# AstroEQ_PTH_MK2.net
KiCad netlist of a schematic drawn in EAGLE
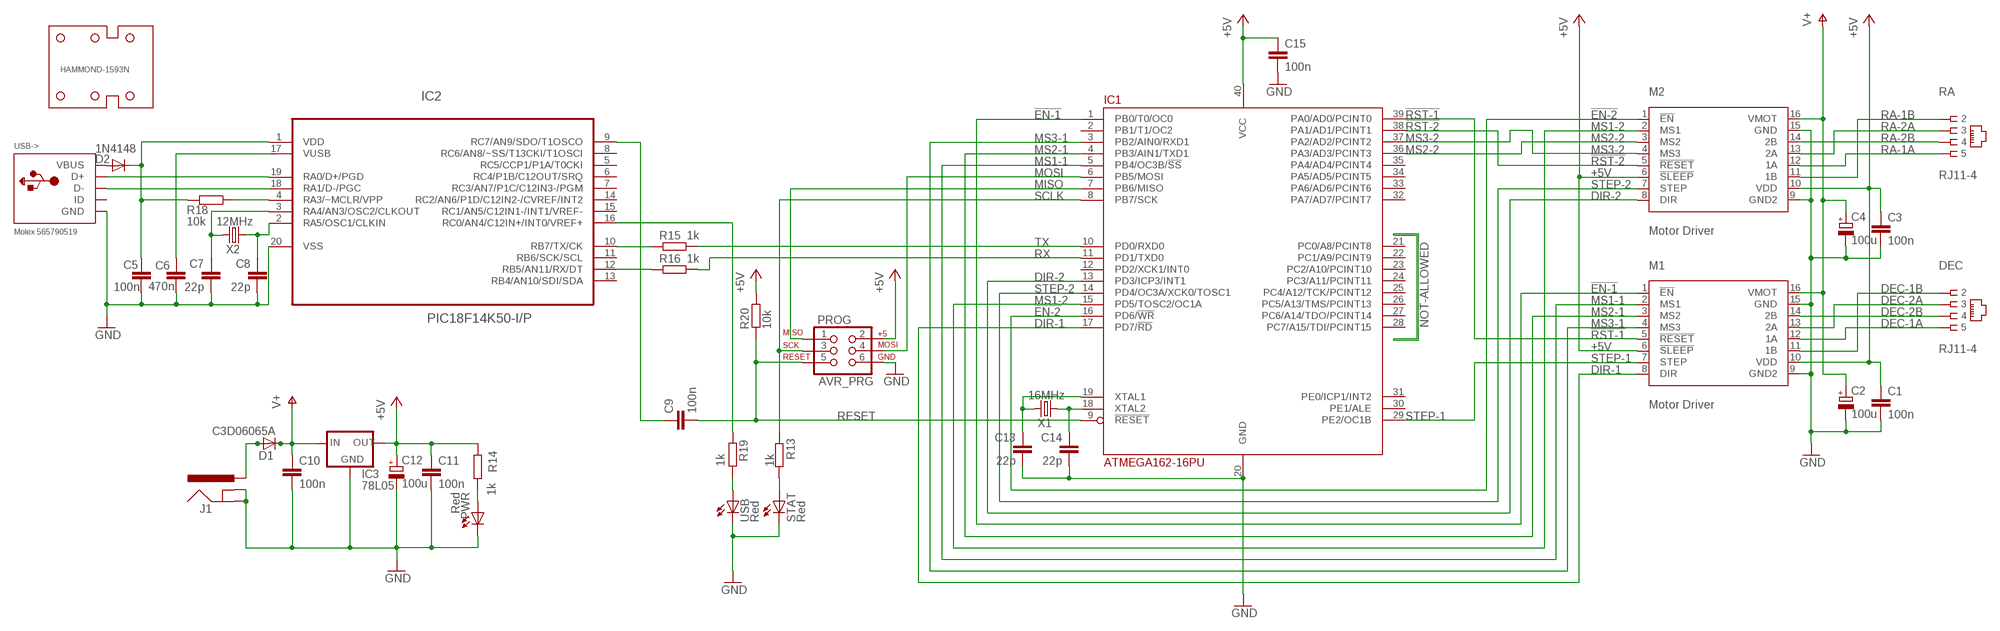
[diagram p0: schematic, sheet 1]

(export (version "E")
  (design (tool "Eeschema 10.0.6"))
  (components
    (comp (ref "C1")
      (value "100n")
      (footprint "eagle-import:C025-024X044")
      (fields (field (name "MF") "AVX") (field (name "MPN") "SR205C104KAR"))
      (libsource (lib "eagle-import") (part "resistor_C-EU025-024X044"))
    )
    (comp (ref "C2")
      (value "100u")
      (footprint "eagle-import:E2,5-7")
      (fields (field (name "MF") "MULTICOMP") (field (name "MPN") "MCGPR25V107M6.3X11"))
      (libsource (lib "eagle-import") (part "CPOL-EUE2.5-7"))
    )
    (comp (ref "C3")
      (value "100n")
      (footprint "eagle-import:C025-024X044")
      (fields (field (name "MF") "AVX") (field (name "MPN") "SR205C104KAR"))
      (libsource (lib "eagle-import") (part "resistor_C-EU025-024X044"))
    )
    (comp (ref "C4")
      (value "100u")
      (footprint "eagle-import:E2,5-7")
      (fields (field (name "MF") "MULTICOMP") (field (name "MPN") "MCGPR25V107M6.3X11"))
      (libsource (lib "eagle-import") (part "CPOL-EUE2.5-7"))
    )
    (comp (ref "C5")
      (value "100n")
      (footprint "eagle-import:C025-024X044")
      (fields (field (name "MF") "AVX") (field (name "MPN") "SR205C104KAR"))
      (libsource (lib "eagle-import") (part "resistor_C-EU025-024X044"))
    )
    (comp (ref "C6")
      (value "470n")
      (footprint "eagle-import:C025-024X044")
      (fields (field (name "MF") "KEMET") (field (name "MPN") "C320C474M5U5TA"))
      (libsource (lib "eagle-import") (part "C-EU025-024X044"))
    )
    (comp (ref "C7")
      (value "22p")
      (footprint "eagle-import:C025-024X044")
      (fields (field (name "MF") "AVX") (field (name "MPN") "SR151A220JAR"))
      (libsource (lib "eagle-import") (part "C-EU025-024X044"))
    )
    (comp (ref "C8")
      (value "22p")
      (footprint "eagle-import:C025-024X044")
      (fields (field (name "MF") "AVX") (field (name "MPN") "SR151A220JAR"))
      (libsource (lib "eagle-import") (part "C-EU025-024X044"))
    )
    (comp (ref "C9")
      (value "100n")
      (footprint "eagle-import:C025-024X044")
      (fields (field (name "MF") "AVX") (field (name "MPN") "SR205C104KAR"))
      (libsource (lib "eagle-import") (part "resistor_C-EU025-024X044"))
    )
    (comp (ref "C10")
      (value "100n")
      (footprint "eagle-import:C025-024X044")
      (fields (field (name "MF") "AVX") (field (name "MPN") "SR205C104KAR"))
      (libsource (lib "eagle-import") (part "resistor_C-EU025-024X044"))
    )
    (comp (ref "C11")
      (value "100n")
      (footprint "eagle-import:C025-024X044")
      (fields (field (name "MF") "AVX") (field (name "MPN") "SR205C104KAR"))
      (libsource (lib "eagle-import") (part "resistor_C-EU025-024X044"))
    )
    (comp (ref "C12")
      (value "100u")
      (footprint "eagle-import:E2,5-7")
      (fields (field (name "MF") "MULTICOMP") (field (name "MPN") "MCGPR25V107M6.3X11"))
      (libsource (lib "eagle-import") (part "CPOL-EUE2.5-7"))
    )
    (comp (ref "C13")
      (value "22p")
      (footprint "eagle-import:C025-024X044")
      (fields (field (name "MF") "AVX") (field (name "MPN") "SR151A220JAR"))
      (libsource (lib "eagle-import") (part "C-EU025-024X044"))
    )
    (comp (ref "C14")
      (value "22p")
      (footprint "eagle-import:C025-024X044")
      (fields (field (name "MF") "AVX") (field (name "MPN") "SR151A220JAR"))
      (libsource (lib "eagle-import") (part "C-EU025-024X044"))
    )
    (comp (ref "C15")
      (value "100n")
      (footprint "eagle-import:C025-024X044")
      (fields (field (name "MF") "AVX") (field (name "MPN") "SR205C104KAR"))
      (libsource (lib "eagle-import") (part "resistor_C-EU025-024X044"))
    )
    (comp (ref "D1")
      (value "C3D06065A")
      (footprint "eagle-import:C221B1A")
      (fields (field (name "MF") "CREE"))
      (libsource (lib "eagle-import") (part "MUR820"))
    )
    (comp (ref "D2")
      (value "1N4148")
      (footprint "eagle-import:DIODE-1N4148")
      (fields (field (name "MF") "MULTICOMP") (field (name "MPN") "1N4148."))
      (libsource (lib "eagle-import") (part "DIODE1N4148"))
    )
    (comp (ref "DEC")
      (value "RJ11-4")
      (footprint "eagle-import:RJ11-NO_SHIELD-4")
      (fields (field (name "MF") "MOLEX") (field (name "MPN") "95501-2641"))
      (libsource (lib "eagle-import") (part "RJ11-4"))
    )
    (comp (ref "HAMMOND-1593N")
      (value "HAMMOND-1593N")
      (footprint "eagle-import:HAMMOND-1593N")
      (fields (field (name "MF") "HAMMOND") (field (name "MPN") "1593NBK"))
      (libsource (lib "eagle-import") (part "HAMMOND-1593N"))
    )
    (comp (ref "IC1")
      (value "ATMEGA162-16PU")
      (footprint "eagle-import:DIL40")
      (fields (field (name "MF") "ATMEL"))
      (libsource (lib "eagle-import") (part "ATMEGA162-16PU"))
    )
    (comp (ref "IC2")
      (value "PIC18F14K50-I/P")
      (footprint "eagle-import:DIL20")
      (fields (field (name "MF") "MICROCHIP"))
      (libsource (lib "eagle-import") (part "PIC18F14K50-I/P"))
    )
    (comp (ref "IC3")
      (value "78L05")
      (footprint "eagle-import:TO-92")
      (fields (field (name "MF") "FAIRCHILD SEMICONDUCTOR") (field (name "MPN") "LM78L05ACZX"))
      (libsource (lib "eagle-import") (part "V_REG_78XXTO-92"))
    )
    (comp (ref "J1")
      (value "POWER_JACKPTH")
      (footprint "eagle-import:POWER_JACK_PTH")
      (fields (field (name "MF") "MULTICOMP") (field (name "MPN") "MJ-179PH"))
      (libsource (lib "eagle-import") (part "POWER_JACKPTH"))
    )
    (comp (ref "M1")
      (value "Motor Driver")
      (footprint "eagle-import:DIP16-W")
      (fields (field (name "MF") "SAMTEC") (field (name "MPN") "CES-116-01-T-S"))
      (libsource (lib "eagle-import") (part "A4983CARRIER"))
    )
    (comp (ref "M2")
      (value "Motor Driver")
      (footprint "eagle-import:DIP16-W")
      (fields (field (name "MF") "SAMTEC") (field (name "MPN") "CES-116-01-T-S"))
      (libsource (lib "eagle-import") (part "A4983CARRIER"))
    )
    (comp (ref "PROG")
      (value "AVR_PRG")
      (footprint "eagle-import:2X3")
      (fields (field (name "MF") "TE CONNECTIVITY / AMP") (field (name "MPN") "826632-3"))
      (libsource (lib "eagle-import") (part "AVR_SPI_PRG_6PTH"))
    )
    (comp (ref "PWR")
      (value "Red")
      (footprint "eagle-import:LED3MM")
      (fields (field (name "MF") "KINGBRIGHT") (field (name "MPN") "L-424HDT"))
      (libsource (lib "eagle-import") (part "LED3MM"))
    )
    (comp (ref "R13")
      (value "1k")
      (footprint "eagle-import:0204_7")
      (fields (field (name "MF") "MULTICOMP") (field (name "MPN") "MF12 1K"))
      (libsource (lib "eagle-import") (part "rcl_R-EU_0204/7"))
    )
    (comp (ref "R14")
      (value "1k")
      (footprint "eagle-import:0204_7")
      (fields (field (name "MF") "MULTICOMP") (field (name "MPN") "MF12 1K"))
      (libsource (lib "eagle-import") (part "rcl_R-EU_0204/7"))
    )
    (comp (ref "R15")
      (value "1k")
      (footprint "eagle-import:0204_7")
      (fields (field (name "MF") "MULTICOMP") (field (name "MPN") "MF12 1K"))
      (libsource (lib "eagle-import") (part "R-EU_0204/7"))
    )
    (comp (ref "R16")
      (value "1k")
      (footprint "eagle-import:0204_7")
      (fields (field (name "MF") "MULTICOMP") (field (name "MPN") "MF12 1K"))
      (libsource (lib "eagle-import") (part "R-EU_0204/7"))
    )
    (comp (ref "R18")
      (value "10k")
      (footprint "eagle-import:0204_7")
      (fields (field (name "MF") "MULTICOMP") (field (name "MPN") "MF12 10K"))
      (libsource (lib "eagle-import") (part "rcl_R-EU_0204/7"))
    )
    (comp (ref "R19")
      (value "1k")
      (footprint "eagle-import:0204_7")
      (fields (field (name "MF") "MULTICOMP") (field (name "MPN") "MF12 1K"))
      (libsource (lib "eagle-import") (part "rcl_R-EU_0204/7"))
    )
    (comp (ref "R20")
      (value "10k")
      (footprint "eagle-import:0204_7")
      (fields (field (name "MF") "MULTICOMP") (field (name "MPN") "MF12 10K"))
      (libsource (lib "eagle-import") (part "rcl_R-EU_0204/7"))
    )
    (comp (ref "RA")
      (value "RJ11-4")
      (footprint "eagle-import:RJ11-NO_SHIELD-4")
      (fields (field (name "MF") "MOLEX") (field (name "MPN") "95501-2641"))
      (libsource (lib "eagle-import") (part "RJ11-4"))
    )
    (comp (ref "STAT")
      (value "Red")
      (footprint "eagle-import:LED3MM")
      (fields (field (name "MF") "KINGBRIGHT") (field (name "MPN") "L-424HDT"))
      (libsource (lib "eagle-import") (part "LED3MM"))
    )
    (comp (ref "USB")
      (value "Red")
      (footprint "eagle-import:LED3MM")
      (fields (field (name "MF") "KINGBRIGHT") (field (name "MPN") "L-424HDT"))
      (libsource (lib "eagle-import") (part "LED3MM"))
    )
    (comp (ref "USB->")
      (value "Molex 565790519")
      (footprint "eagle-import:USB-MINIB-THM-MOLEX")
      (fields (field (name "MF") "MOLEX") (field (name "MPN") "565790519"))
      (libsource (lib "eagle-import") (part "USBMOLEX"))
    )
    (comp (ref "X1")
      (value "16MHz")
      (footprint "eagle-import:HC49US")
      (fields (field (name "MF") "TXC") (field (name "MPN") "9B-16.000MEEJ-B"))
      (libsource (lib "eagle-import") (part "CRYSTALHC49US"))
    )
    (comp (ref "X2")
      (value "12MHz")
      (footprint "eagle-import:HC49US")
      (fields (field (name "MF") "TXC") (field (name "MPN") "9B-12.000MAAJ-B"))
      (libsource (lib "eagle-import") (part "CRYSTALHC49US"))
    )
  )
  (nets
    (net (code "1") (name "+5V") (class "Default")
      (node (ref "C1") (pin "1") (pinfunction "1_1") (pintype "passive"))
      (node (ref "C11") (pin "1") (pinfunction "1_1") (pintype "passive"))
      (node (ref "C12") (pin "+") (pinfunction "+_+") (pintype "passive"))
      (node (ref "C15") (pin "1") (pinfunction "1_1") (pintype "passive"))
      (node (ref "C3") (pin "1") (pinfunction "1_1") (pintype "passive"))
      (node (ref "IC1") (pin "40") (pinfunction "VCC_40") (pintype "power_in"))
      (node (ref "IC3") (pin "1") (pinfunction "OUT_1") (pintype "power_in"))
      (node (ref "M1") (pin "10") (pinfunction "VDD_10") (pintype "power_in"))
      (node (ref "M1") (pin "6") (pinfunction "~{SLEEP}_6") (pintype "input"))
      (node (ref "M2") (pin "10") (pinfunction "VDD_10") (pintype "power_in"))
      (node (ref "M2") (pin "6") (pinfunction "~{SLEEP}_6") (pintype "input"))
      (node (ref "PROG") (pin "2") (pinfunction "2_2") (pintype "passive"))
      (node (ref "R14") (pin "1") (pinfunction "1_1") (pintype "passive"))
      (node (ref "R20") (pin "2") (pinfunction "2_2") (pintype "passive"))
    )
    (net (code "2") (name "/DEC-1A") (class "Default")
      (node (ref "DEC") (pin "5") (pinfunction "5_5") (pintype "passive"))
      (node (ref "M1") (pin "12") (pinfunction "1A_12") (pintype "output"))
    )
    (net (code "3") (name "/DEC-1B") (class "Default")
      (node (ref "DEC") (pin "2") (pinfunction "2_2") (pintype "passive"))
      (node (ref "M1") (pin "11") (pinfunction "1B_11") (pintype "output"))
    )
    (net (code "4") (name "/DEC-2A") (class "Default")
      (node (ref "DEC") (pin "3") (pinfunction "3_3") (pintype "passive"))
      (node (ref "M1") (pin "13") (pinfunction "2A_13") (pintype "output"))
    )
    (net (code "5") (name "/DEC-2B") (class "Default")
      (node (ref "DEC") (pin "4") (pinfunction "4_4") (pintype "passive"))
      (node (ref "M1") (pin "14") (pinfunction "2B_14") (pintype "output"))
    )
    (net (code "6") (name "/DIR-1") (class "Default")
      (node (ref "IC1") (pin "17") (pinfunction "PD7/~{RD}_17") (pintype "bidirectional"))
      (node (ref "M1") (pin "8") (pinfunction "DIR_8") (pintype "input"))
    )
    (net (code "7") (name "/DIR-2") (class "Default")
      (node (ref "IC1") (pin "13") (pinfunction "PD3/ICP3/INT1_13") (pintype "bidirectional"))
      (node (ref "M2") (pin "8") (pinfunction "DIR_8") (pintype "input"))
    )
    (net (code "8") (name "/MISO") (class "Default")
      (node (ref "IC1") (pin "7") (pinfunction "PB6/MISO_7") (pintype "bidirectional"))
      (node (ref "PROG") (pin "1") (pinfunction "1_1") (pintype "passive"))
    )
    (net (code "9") (name "/MOSI") (class "Default")
      (node (ref "IC1") (pin "6") (pinfunction "PB5/MOSI_6") (pintype "bidirectional"))
      (node (ref "PROG") (pin "4") (pinfunction "4_4") (pintype "passive"))
    )
    (net (code "10") (name "/MS1-1") (class "Default")
      (node (ref "IC1") (pin "5") (pinfunction "PB4/OC3B/~{SS}_5") (pintype "bidirectional"))
      (node (ref "M1") (pin "2") (pinfunction "MS1_2") (pintype "input"))
    )
    (net (code "11") (name "/MS1-2") (class "Default")
      (node (ref "IC1") (pin "15") (pinfunction "PD5/TOSC2/OC1A_15") (pintype "bidirectional"))
      (node (ref "M2") (pin "2") (pinfunction "MS1_2") (pintype "input"))
    )
    (net (code "12") (name "/MS2-1") (class "Default")
      (node (ref "IC1") (pin "4") (pinfunction "PB3/AIN1/TXD1_4") (pintype "bidirectional"))
      (node (ref "M1") (pin "3") (pinfunction "MS2_3") (pintype "input"))
    )
    (net (code "13") (name "/MS2-2") (class "Default")
      (node (ref "IC1") (pin "36") (pinfunction "PA3/AD3/PCINT3_36") (pintype "bidirectional"))
      (node (ref "M2") (pin "3") (pinfunction "MS2_3") (pintype "input"))
    )
    (net (code "14") (name "/MS3-1") (class "Default")
      (node (ref "IC1") (pin "3") (pinfunction "PB2/AIN0/RXD1_3") (pintype "bidirectional"))
      (node (ref "M1") (pin "4") (pinfunction "MS3_4") (pintype "input"))
    )
    (net (code "15") (name "/MS3-2") (class "Default")
      (node (ref "IC1") (pin "37") (pinfunction "PA2/AD2/PCINT2_37") (pintype "bidirectional"))
      (node (ref "M2") (pin "4") (pinfunction "MS3_4") (pintype "input"))
    )
    (net (code "16") (name "/RA-1A") (class "Default")
      (node (ref "M2") (pin "12") (pinfunction "1A_12") (pintype "output"))
      (node (ref "RA") (pin "5") (pinfunction "5_5") (pintype "passive"))
    )
    (net (code "17") (name "/RA-1B") (class "Default")
      (node (ref "M2") (pin "11") (pinfunction "1B_11") (pintype "output"))
      (node (ref "RA") (pin "2") (pinfunction "2_2") (pintype "passive"))
    )
    (net (code "18") (name "/RA-2A") (class "Default")
      (node (ref "M2") (pin "13") (pinfunction "2A_13") (pintype "output"))
      (node (ref "RA") (pin "3") (pinfunction "3_3") (pintype "passive"))
    )
    (net (code "19") (name "/RA-2B") (class "Default")
      (node (ref "M2") (pin "14") (pinfunction "2B_14") (pintype "output"))
      (node (ref "RA") (pin "4") (pinfunction "4_4") (pintype "passive"))
    )
    (net (code "20") (name "/RESET") (class "Default")
      (node (ref "C9") (pin "2") (pinfunction "2_2") (pintype "passive"))
      (node (ref "IC1") (pin "9") (pinfunction "~{RESET}_9") (pintype "input"))
      (node (ref "PROG") (pin "5") (pinfunction "5_5") (pintype "passive"))
      (node (ref "R20") (pin "1") (pinfunction "1_1") (pintype "passive"))
    )
    (net (code "21") (name "/RX") (class "Default")
      (node (ref "IC1") (pin "11") (pinfunction "PD1/TXD0_11") (pintype "bidirectional"))
      (node (ref "R16") (pin "1") (pinfunction "1_1") (pintype "passive"))
    )
    (net (code "22") (name "/SCLK") (class "Default")
      (node (ref "IC1") (pin "8") (pinfunction "PB7/SCK_8") (pintype "bidirectional"))
      (node (ref "PROG") (pin "3") (pinfunction "3_3") (pintype "passive"))
      (node (ref "R13") (pin "1") (pinfunction "1_1") (pintype "passive"))
    )
    (net (code "23") (name "/STEP-1") (class "Default")
      (node (ref "IC1") (pin "29") (pinfunction "PE2/OC1B_29") (pintype "bidirectional"))
      (node (ref "M1") (pin "7") (pinfunction "STEP_7") (pintype "input"))
    )
    (net (code "24") (name "/STEP-2") (class "Default")
      (node (ref "IC1") (pin "14") (pinfunction "PD4/OC3A/XCK0/TOSC1_14") (pintype "bidirectional"))
      (node (ref "M2") (pin "7") (pinfunction "STEP_7") (pintype "input"))
    )
    (net (code "25") (name "/TX") (class "Default")
      (node (ref "IC1") (pin "10") (pinfunction "PD0/RXD0_10") (pintype "bidirectional"))
      (node (ref "R15") (pin "1") (pinfunction "1_1") (pintype "passive"))
    )
    (net (code "26") (name "/~{EN-1}") (class "Default")
      (node (ref "IC1") (pin "1") (pinfunction "PB0/T0/OC0_1") (pintype "bidirectional"))
      (node (ref "M1") (pin "1") (pinfunction "~{EN}_1") (pintype "input"))
    )
    (net (code "27") (name "/~{EN-2}") (class "Default")
      (node (ref "IC1") (pin "16") (pinfunction "PD6/~{WR}_16") (pintype "bidirectional"))
      (node (ref "M2") (pin "1") (pinfunction "~{EN}_1") (pintype "input"))
    )
    (net (code "29") (name "/~{RST-1}") (class "Default")
      (node (ref "IC1") (pin "39") (pinfunction "PA0/AD0/PCINT0_39") (pintype "bidirectional"))
      (node (ref "M1") (pin "5") (pinfunction "~{RESET}_5") (pintype "input"))
    )
    (net (code "30") (name "/~{RST-2}") (class "Default")
      (node (ref "IC1") (pin "38") (pinfunction "PA1/AD1/PCINT1_38") (pintype "bidirectional"))
      (node (ref "M2") (pin "5") (pinfunction "~{RESET}_5") (pintype "input"))
    )
    (net (code "31") (name "GND") (class "Default")
      (node (ref "C1") (pin "2") (pinfunction "2_2") (pintype "passive"))
      (node (ref "C10") (pin "2") (pinfunction "2_2") (pintype "passive"))
      (node (ref "C11") (pin "2") (pinfunction "2_2") (pintype "passive"))
      (node (ref "C12") (pin "-") (pinfunction "-_-") (pintype "passive"))
      (node (ref "C13") (pin "2") (pinfunction "2_2") (pintype "passive"))
      (node (ref "C14") (pin "2") (pinfunction "2_2") (pintype "passive"))
      (node (ref "C15") (pin "2") (pinfunction "2_2") (pintype "passive"))
      (node (ref "C2") (pin "-") (pinfunction "-_-") (pintype "passive"))
      (node (ref "C3") (pin "2") (pinfunction "2_2") (pintype "passive"))
      (node (ref "C4") (pin "-") (pinfunction "-_-") (pintype "passive"))
      (node (ref "C5") (pin "2") (pinfunction "2_2") (pintype "passive"))
      (node (ref "C6") (pin "1") (pinfunction "1_1") (pintype "passive"))
      (node (ref "C7") (pin "2") (pinfunction "2_2") (pintype "passive"))
      (node (ref "C8") (pin "2") (pinfunction "2_2") (pintype "passive"))
      (node (ref "IC1") (pin "20") (pinfunction "GND_20") (pintype "power_in"))
      (node (ref "IC2") (pin "20") (pinfunction "VSS_20") (pintype "power_in"))
      (node (ref "IC3") (pin "2") (pinfunction "GND_2") (pintype "input"))
      (node (ref "J1") (pin "GND") (pinfunction "GND_GND") (pintype "bidirectional"))
      (node (ref "J1") (pin "GNDBREAK") (pinfunction "GNDBREAK_GNDBREAK") (pintype "bidirectional"))
      (node (ref "M1") (pin "15") (pinfunction "GND_15") (pintype "power_in"))
      (node (ref "M1") (pin "9") (pinfunction "GND2_9") (pintype "power_in"))
      (node (ref "M2") (pin "15") (pinfunction "GND_15") (pintype "power_in"))
      (node (ref "M2") (pin "9") (pinfunction "GND2_9") (pintype "power_in"))
      (node (ref "PROG") (pin "6") (pinfunction "6_6") (pintype "passive"))
      (node (ref "PWR") (pin "K") (pinfunction "C_K") (pintype "passive"))
      (node (ref "STAT") (pin "K") (pinfunction "C_K") (pintype "passive"))
      (node (ref "USB") (pin "K") (pinfunction "C_K") (pintype "passive"))
      (node (ref "USB->") (pin "GND") (pinfunction "GND_GND") (pintype "power_in"))
      (node (ref "USB->") (pin "GND1") (pinfunction "GND_GND1") (pintype "power_in"))
      (node (ref "USB->") (pin "GND4") (pinfunction "GND_GND4") (pintype "power_in"))
    )
    (net (code "32") (name "Net-(D1-PadA)") (class "Default")
      (node (ref "D1") (pin "A") (pinfunction "A_A") (pintype "passive"))
      (node (ref "J1") (pin "PWR") (pinfunction "PWR_PWR") (pintype "bidirectional"))
    )
    (net (code "33") (name "Net-(D2-PadA)") (class "Default")
      (node (ref "D2") (pin "A") (pinfunction "A_A") (pintype "passive"))
      (node (ref "USB->") (pin "VBUS") (pinfunction "VBUS_VBUS") (pintype "power_in"))
    )
    (net (code "34") (name "Net-(IC1-XTAL1)") (class "Default")
      (node (ref "C13") (pin "1") (pinfunction "1_1") (pintype "passive"))
      (node (ref "IC1") (pin "19") (pinfunction "XTAL1_19") (pintype "input"))
      (node (ref "X1") (pin "2") (pinfunction "2_2") (pintype "passive"))
    )
    (net (code "35") (name "Net-(IC1-XTAL2)") (class "Default")
      (node (ref "C14") (pin "1") (pinfunction "1_1") (pintype "passive"))
      (node (ref "IC1") (pin "18") (pinfunction "XTAL2_18") (pintype "input"))
      (node (ref "X1") (pin "1") (pinfunction "1_1") (pintype "passive"))
    )
    (net (code "36") (name "Net-(IC2-RA0{slash}D+{slash}PGD)") (class "Default")
      (node (ref "IC2") (pin "19") (pinfunction "RA0/D+/PGD_19") (pintype "bidirectional"))
      (node (ref "USB->") (pin "D+") (pinfunction "D+_D+") (pintype "bidirectional"))
    )
    (net (code "37") (name "Net-(IC2-RA1{slash}D-{slash}PGC)") (class "Default")
      (node (ref "IC2") (pin "18") (pinfunction "RA1/D-/PGC_18") (pintype "bidirectional"))
      (node (ref "USB->") (pin "D-") (pinfunction "D-_D-") (pintype "bidirectional"))
    )
    (net (code "38") (name "Net-(IC2-RA3{slash}~{MCLR{slash}VPP})") (class "Default")
      (node (ref "IC2") (pin "4") (pinfunction "RA3/~{MCLR/VPP}_4") (pintype "input"))
      (node (ref "R18") (pin "1") (pinfunction "1_1") (pintype "passive"))
    )
    (net (code "39") (name "Net-(IC2-RA4{slash}AN3{slash}OSC2{slash}CLKOUT)") (class "Default")
      (node (ref "C7") (pin "1") (pinfunction "1_1") (pintype "passive"))
      (node (ref "IC2") (pin "3") (pinfunction "RA4/AN3/OSC2/CLKOUT_3") (pintype "bidirectional"))
      (node (ref "X2") (pin "2") (pinfunction "2_2") (pintype "passive"))
    )
    (net (code "40") (name "Net-(IC2-RA5{slash}OSC1{slash}CLKIN)") (class "Default")
      (node (ref "C8") (pin "1") (pinfunction "1_1") (pintype "passive"))
      (node (ref "IC2") (pin "2") (pinfunction "RA5/OSC1/CLKIN_2") (pintype "bidirectional"))
      (node (ref "X2") (pin "1") (pinfunction "1_1") (pintype "passive"))
    )
    (net (code "41") (name "Net-(IC2-RB5{slash}AN11{slash}RX{slash}DT)") (class "Default")
      (node (ref "IC2") (pin "12") (pinfunction "RB5/AN11/RX/DT_12") (pintype "bidirectional"))
      (node (ref "R16") (pin "2") (pinfunction "2_2") (pintype "passive"))
    )
    (net (code "42") (name "Net-(IC2-RB7{slash}TX{slash}CK)") (class "Default")
      (node (ref "IC2") (pin "10") (pinfunction "RB7/TX/CK_10") (pintype "bidirectional"))
      (node (ref "R15") (pin "2") (pinfunction "2_2") (pintype "passive"))
    )
    (net (code "43") (name "Net-(IC2-RC0{slash}AN4{slash}C12IN+{slash}INT0{slash}VREF+)") (class "Default")
      (node (ref "IC2") (pin "16") (pinfunction "RC0/AN4/C12IN+/INT0/VREF+_16") (pintype "bidirectional"))
      (node (ref "R19") (pin "2") (pinfunction "2_2") (pintype "passive"))
    )
    (net (code "44") (name "Net-(IC2-RC7{slash}AN9{slash}SDO{slash}T1OSCO)") (class "Default")
      (node (ref "C9") (pin "1") (pinfunction "1_1") (pintype "passive"))
      (node (ref "IC2") (pin "9") (pinfunction "RC7/AN9/SDO/T1OSCO_9") (pintype "bidirectional"))
    )
    (net (code "45") (name "Net-(IC2-VDD)") (class "Default")
      (node (ref "C5") (pin "1") (pinfunction "1_1") (pintype "passive"))
      (node (ref "D2") (pin "C") (pinfunction "C_C") (pintype "passive"))
      (node (ref "IC2") (pin "1") (pinfunction "VDD_1") (pintype "power_in"))
      (node (ref "R18") (pin "2") (pinfunction "2_2") (pintype "passive"))
    )
    (net (code "46") (name "Net-(IC2-VUSB)") (class "Default")
      (node (ref "C6") (pin "2") (pinfunction "2_2") (pintype "passive"))
      (node (ref "IC2") (pin "17") (pinfunction "VUSB_17") (pintype "power_in"))
    )
    (net (code "47") (name "Net-(PWR-PadA)") (class "Default")
      (node (ref "PWR") (pin "A") (pinfunction "A_A") (pintype "passive"))
      (node (ref "R14") (pin "2") (pinfunction "2_2") (pintype "passive"))
    )
    (net (code "48") (name "Net-(R13-Pad2)") (class "Default")
      (node (ref "R13") (pin "2") (pinfunction "2_2") (pintype "passive"))
      (node (ref "STAT") (pin "A") (pinfunction "A_A") (pintype "passive"))
    )
    (net (code "49") (name "Net-(R19-Pad1)") (class "Default")
      (node (ref "R19") (pin "1") (pinfunction "1_1") (pintype "passive"))
      (node (ref "USB") (pin "A") (pinfunction "A_A") (pintype "passive"))
    )
    (net (code "50") (name "V+") (class "Default")
      (node (ref "C10") (pin "1") (pinfunction "1_1") (pintype "passive"))
      (node (ref "C2") (pin "+") (pinfunction "+_+") (pintype "passive"))
      (node (ref "C4") (pin "+") (pinfunction "+_+") (pintype "passive"))
      (node (ref "D1") (pin "C") (pinfunction "C_C") (pintype "passive"))
      (node (ref "IC3") (pin "3") (pinfunction "IN_3") (pintype "input"))
      (node (ref "M1") (pin "16") (pinfunction "VMOT_16") (pintype "power_in"))
      (node (ref "M2") (pin "16") (pinfunction "VMOT_16") (pintype "power_in"))
    )
    (net (code "51") (name "unconnected-(IC1-PA4{slash}AD4{slash}PCINT4-Pad35)") (class "Default")
      (node (ref "IC1") (pin "35") (pinfunction "PA4/AD4/PCINT4_35") (pintype "bidirectional"))
    )
    (net (code "52") (name "unconnected-(IC1-PA5{slash}AD5{slash}PCINT5-Pad34)") (class "Default")
      (node (ref "IC1") (pin "34") (pinfunction "PA5/AD5/PCINT5_34") (pintype "bidirectional"))
    )
    (net (code "53") (name "unconnected-(IC1-PA6{slash}AD6{slash}PCINT6-Pad33)") (class "Default")
      (node (ref "IC1") (pin "33") (pinfunction "PA6/AD6/PCINT6_33") (pintype "bidirectional"))
    )
    (net (code "54") (name "unconnected-(IC1-PA7{slash}AD7{slash}PCINT7-Pad32)") (class "Default")
      (node (ref "IC1") (pin "32") (pinfunction "PA7/AD7/PCINT7_32") (pintype "bidirectional"))
    )
    (net (code "55") (name "unconnected-(IC1-PB1{slash}T1{slash}OC2-Pad2)") (class "Default")
      (node (ref "IC1") (pin "2") (pinfunction "PB1/T1/OC2_2") (pintype "bidirectional"))
    )
    (net (code "56") (name "unconnected-(IC1-PC0{slash}A8{slash}PCINT8-Pad21)") (class "Default")
      (node (ref "IC1") (pin "21") (pinfunction "PC0/A8/PCINT8_21") (pintype "bidirectional"))
    )
    (net (code "57") (name "unconnected-(IC1-PC1{slash}A9{slash}PCINT9-Pad22)") (class "Default")
      (node (ref "IC1") (pin "22") (pinfunction "PC1/A9/PCINT9_22") (pintype "bidirectional"))
    )
    (net (code "58") (name "unconnected-(IC1-PC2{slash}A10{slash}PCINT10-Pad23)") (class "Default")
      (node (ref "IC1") (pin "23") (pinfunction "PC2/A10/PCINT10_23") (pintype "bidirectional"))
    )
    (net (code "59") (name "unconnected-(IC1-PC3{slash}A11{slash}PCINT11-Pad24)") (class "Default")
      (node (ref "IC1") (pin "24") (pinfunction "PC3/A11/PCINT11_24") (pintype "bidirectional"))
    )
    (net (code "60") (name "unconnected-(IC1-PC4{slash}A12{slash}TCK{slash}PCINT12-Pad25)") (class "Default")
      (node (ref "IC1") (pin "25") (pinfunction "PC4/A12/TCK/PCINT12_25") (pintype "bidirectional"))
    )
    (net (code "61") (name "unconnected-(IC1-PC5{slash}A13{slash}TMS{slash}PCINT13-Pad26)") (class "Default")
      (node (ref "IC1") (pin "26") (pinfunction "PC5/A13/TMS/PCINT13_26") (pintype "bidirectional"))
    )
    (net (code "62") (name "unconnected-(IC1-PC6{slash}A14{slash}TDO{slash}PCINT14-Pad27)") (class "Default")
      (node (ref "IC1") (pin "27") (pinfunction "PC6/A14/TDO/PCINT14_27") (pintype "bidirectional"))
    )
    (net (code "63") (name "unconnected-(IC1-PC7{slash}A15{slash}TDI{slash}PCINT15-Pad28)") (class "Default")
      (node (ref "IC1") (pin "28") (pinfunction "PC7/A15/TDI/PCINT15_28") (pintype "bidirectional"))
    )
    (net (code "64") (name "unconnected-(IC1-PD2{slash}XCK1{slash}INT0-Pad12)") (class "Default")
      (node (ref "IC1") (pin "12") (pinfunction "PD2/XCK1/INT0_12") (pintype "bidirectional"))
    )
    (net (code "65") (name "unconnected-(IC1-PE0{slash}ICP1{slash}INT2-Pad31)") (class "Default")
      (node (ref "IC1") (pin "31") (pinfunction "PE0/ICP1/INT2_31") (pintype "bidirectional"))
    )
    (net (code "66") (name "unconnected-(IC1-PE1{slash}ALE-Pad30)") (class "Default")
      (node (ref "IC1") (pin "30") (pinfunction "PE1/ALE_30") (pintype "bidirectional"))
    )
    (net (code "67") (name "unconnected-(IC2-RB4{slash}AN10{slash}SDI{slash}SDA-Pad13)") (class "Default")
      (node (ref "IC2") (pin "13") (pinfunction "RB4/AN10/SDI/SDA_13") (pintype "bidirectional"))
    )
    (net (code "68") (name "unconnected-(IC2-RB6{slash}SCK{slash}SCL-Pad11)") (class "Default")
      (node (ref "IC2") (pin "11") (pinfunction "RB6/SCK/SCL_11") (pintype "bidirectional"))
    )
    (net (code "69") (name "unconnected-(IC2-RC1{slash}AN5{slash}C12IN1-{slash}INT1{slash}VREF--Pad15)") (class "Default")
      (node (ref "IC2") (pin "15") (pinfunction "RC1/AN5/C12IN1-/INT1/VREF-_15") (pintype "bidirectional"))
    )
    (net (code "70") (name "unconnected-(IC2-RC2{slash}AN6{slash}P1D{slash}C12IN2-{slash}CVREF{slash}INT2-Pad14)") (class "Default")
      (node (ref "IC2") (pin "14") (pinfunction "RC2/AN6/P1D/C12IN2-/CVREF/INT2_14") (pintype "bidirectional"))
    )
    (net (code "71") (name "unconnected-(IC2-RC3{slash}AN7{slash}P1C{slash}C12IN3-{slash}PGM-Pad7)") (class "Default")
      (node (ref "IC2") (pin "7") (pinfunction "RC3/AN7/P1C/C12IN3-/PGM_7") (pintype "bidirectional"))
    )
    (net (code "72") (name "unconnected-(IC2-RC4{slash}P1B{slash}C12OUT{slash}SRQ-Pad6)") (class "Default")
      (node (ref "IC2") (pin "6") (pinfunction "RC4/P1B/C12OUT/SRQ_6") (pintype "bidirectional"))
    )
    (net (code "73") (name "unconnected-(IC2-RC5{slash}CCP1{slash}P1A{slash}T0CKI-Pad5)") (class "Default")
      (node (ref "IC2") (pin "5") (pinfunction "RC5/CCP1/P1A/T0CKI_5") (pintype "bidirectional"))
    )
    (net (code "74") (name "unconnected-(IC2-RC6{slash}AN8{slash}~{SS{slash}T13CKI{slash}T1OSCI}-Pad8)") (class "Default")
      (node (ref "IC2") (pin "8") (pinfunction "RC6/AN8/~{SS/T13CKI/T1OSCI}_8") (pintype "bidirectional"))
    )
    (net (code "75") (name "unconnected-(USB->-PadID)") (class "Default")
      (node (ref "USB->") (pin "ID") (pinfunction "ID_ID") (pintype "bidirectional"))
    )
  )
)
